# wien.net
KiCad netlist of a schematic drawn in EAGLE
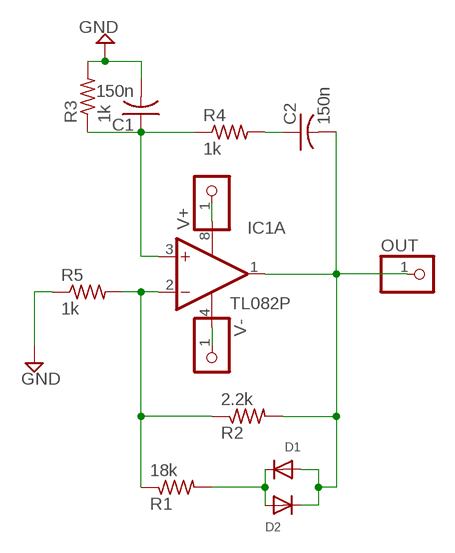
[diagram p0: schematic, sheet 1]

(export (version "E")
  (design (tool "Eeschema 10.0.6"))
  (components
    (comp (ref "C1")
      (value "150n")
      (footprint "eagle-import:C025-030X050")
      (libsource (lib "eagle-import") (part "C-US025-030X050"))
    )
    (comp (ref "C2")
      (value "150n")
      (footprint "eagle-import:C025-030X050")
      (libsource (lib "eagle-import") (part "C-US025-030X050"))
    )
    (comp (ref "D1")
      (value "DIODEDO-1N4148")
      (footprint "eagle-import:DO-1N4148")
      (libsource (lib "eagle-import") (part "DIODEDO-1N4148"))
    )
    (comp (ref "D2")
      (value "DIODEDO-1N4148")
      (footprint "eagle-import:DO-1N4148")
      (libsource (lib "eagle-import") (part "DIODEDO-1N4148"))
    )
    (comp (ref "IC1")
      (value "TL082P")
      (footprint "eagle-import:DIL08")
      (libsource (lib "eagle-import") (part "TL082P"))
    )
    (comp (ref "OUT")
      (value "PINHD-1X1CB")
      (footprint "eagle-import:1X01-CLEANBIG")
      (libsource (lib "eagle-import") (part "PINHD-1X1CB"))
    )
    (comp (ref "R1")
      (value "18k")
      (footprint "eagle-import:0207_12")
      (libsource (lib "eagle-import") (part "R-US_0207/12"))
    )
    (comp (ref "R2")
      (value "2.2k")
      (footprint "eagle-import:0207_12")
      (libsource (lib "eagle-import") (part "R-US_0207/12"))
    )
    (comp (ref "R3")
      (value "1k")
      (footprint "eagle-import:0207_12")
      (libsource (lib "eagle-import") (part "R-US_0207/12"))
    )
    (comp (ref "R4")
      (value "1k")
      (footprint "eagle-import:0207_12")
      (libsource (lib "eagle-import") (part "R-US_0207/12"))
    )
    (comp (ref "R5")
      (value "1k")
      (footprint "eagle-import:0207_12")
      (libsource (lib "eagle-import") (part "R-US_0207/12"))
    )
    (comp (ref "V+")
      (value "PINHD-1X1CB")
      (footprint "eagle-import:1X01-CLEANBIG")
      (libsource (lib "eagle-import") (part "PINHD-1X1CB"))
    )
    (comp (ref "V-")
      (value "PINHD-1X1CB")
      (footprint "eagle-import:1X01-CLEANBIG")
      (libsource (lib "eagle-import") (part "PINHD-1X1CB"))
    )
  )
  (nets
    (net (code "1") (name "GND") (class "Default")
      (node (ref "C1") (pin "2") (pinfunction "2_2") (pintype "passive"))
      (node (ref "R3") (pin "2") (pinfunction "2_2") (pintype "passive"))
      (node (ref "R5") (pin "1") (pinfunction "1_1") (pintype "passive"))
    )
    (net (code "2") (name "Net-(C2-Pad1)") (class "Default")
      (node (ref "C2") (pin "1") (pinfunction "1_1") (pintype "passive"))
      (node (ref "R4") (pin "2") (pinfunction "2_2") (pintype "passive"))
    )
    (net (code "3") (name "Net-(D1-PadC)") (class "Default")
      (node (ref "D1") (pin "C") (pinfunction "C_C") (pintype "passive"))
      (node (ref "D2") (pin "A") (pinfunction "A_A") (pintype "passive"))
      (node (ref "R1") (pin "2") (pinfunction "2_2") (pintype "passive"))
    )
    (net (code "4") (name "Net-(IC1A-+IN)") (class "Default")
      (node (ref "C1") (pin "1") (pinfunction "1_1") (pintype "passive"))
      (node (ref "IC1") (pin "3") (pinfunction "+IN_3") (pintype "input"))
      (node (ref "R3") (pin "1") (pinfunction "1_1") (pintype "passive"))
      (node (ref "R4") (pin "1") (pinfunction "1_1") (pintype "passive"))
    )
    (net (code "5") (name "Net-(IC1A--IN)") (class "Default")
      (node (ref "IC1") (pin "2") (pinfunction "-IN_2") (pintype "input"))
      (node (ref "R1") (pin "1") (pinfunction "1_1") (pintype "passive"))
      (node (ref "R2") (pin "1") (pinfunction "1_1") (pintype "passive"))
      (node (ref "R5") (pin "2") (pinfunction "2_2") (pintype "passive"))
    )
    (net (code "6") (name "Net-(IC1A-OUT)") (class "Default")
      (node (ref "C2") (pin "2") (pinfunction "2_2") (pintype "passive"))
      (node (ref "D1") (pin "A") (pinfunction "A_A") (pintype "passive"))
      (node (ref "D2") (pin "C") (pinfunction "C_C") (pintype "passive"))
      (node (ref "IC1") (pin "1") (pinfunction "OUT_1") (pintype "output"))
      (node (ref "OUT") (pin "1") (pinfunction "1_1") (pintype "passive"))
      (node (ref "R2") (pin "2") (pinfunction "2_2") (pintype "passive"))
    )
    (net (code "7") (name "Net-(IC1C-V+)") (class "Default")
      (node (ref "IC1") (pin "8") (pinfunction "V+_8") (pintype "power_in"))
      (node (ref "V+") (pin "1") (pinfunction "1_1") (pintype "passive"))
    )
    (net (code "8") (name "Net-(IC1C-V-)") (class "Default")
      (node (ref "IC1") (pin "4") (pinfunction "V-_4") (pintype "power_in"))
      (node (ref "V-") (pin "1") (pinfunction "1_1") (pintype "passive"))
    )
  )
)
